# RP5_Left_Board.net
KiCad netlist of a schematic drawn in Altium Designer
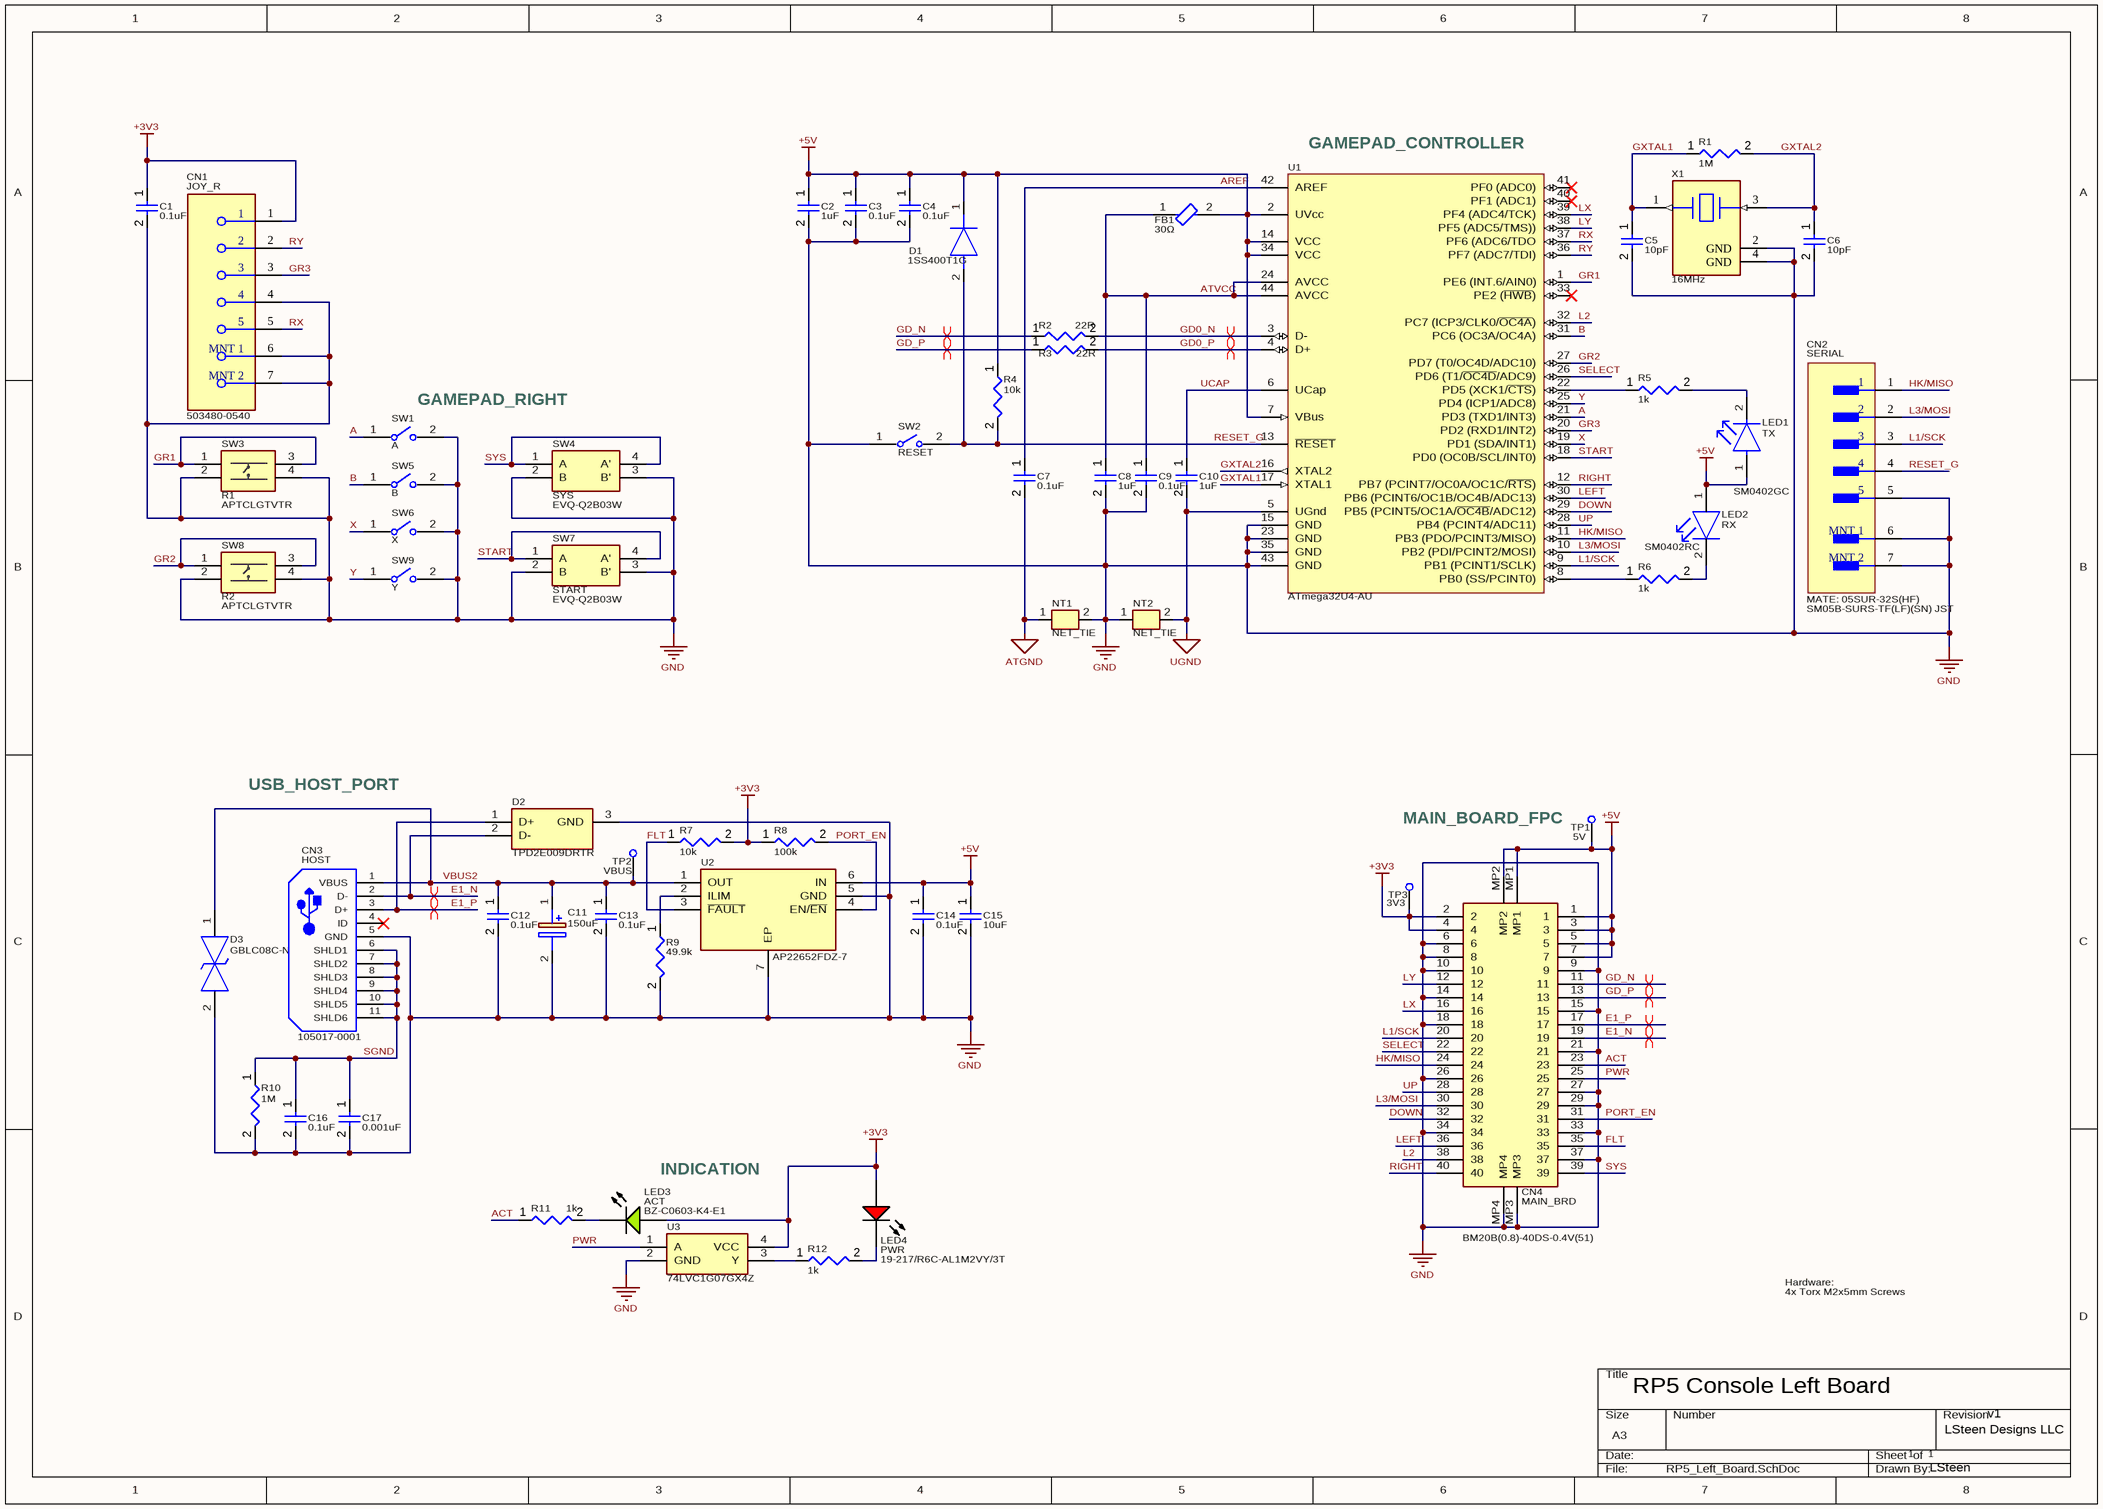
[diagram p0: RP5_Left_Board.SchDoc]

(export (version "E")
  (design (tool "Eeschema 10.0.6"))
  (components
    (comp (ref "C1")
      (value "0.1uF")
      (footprint "CAPC1005X56X25LL10T15")
      (description "Chip Capacitor, 0.1 uF, +/- 5%, 16 V, 0402 (1005 Metric)")
      (fields (field (name "TOLERANCE") "5%"))
      (libsource (lib "Colorado Technical University") (part "CAP-NP-2"))
    )
    (comp (ref "C2")
      (value "1uF")
      (footprint "CAPC0603(1608)100_L")
      (description "Chip Capacitor, 1uF +/-20%, 10V, 0603, Thickness 1 mm")
      (fields (field (name "TOLERANCE") "10%"))
      (libsource (lib "Colorado Technical University") (part "CAP-NP-2"))
    )
    (comp (ref "C3")
      (value "0.1uF")
      (footprint "CAPC1005X56X25LL10T15")
      (description "Chip Capacitor, 0.1 uF, +/- 5%, 16 V, 0402 (1005 Metric)")
      (fields (field (name "TOLERANCE") "5%"))
      (libsource (lib "Colorado Technical University") (part "CAP-NP-2"))
    )
    (comp (ref "C4")
      (value "0.1uF")
      (footprint "CAPC1005X56X25LL10T15")
      (description "Chip Capacitor, 0.1 uF, +/- 5%, 16 V, 0402 (1005 Metric)")
      (fields (field (name "TOLERANCE") "5%"))
      (libsource (lib "Colorado Technical University") (part "CAP-NP-2"))
    )
    (comp (ref "C5")
      (value "10pF")
      (footprint "CAPC1005X56X25LL10T15")
      (description "Chip Capacitor, 10 pF, +/- 5%, 16 V, 0402 (1005 Metric)")
      (fields (field (name "TOLERANCE") "5%"))
      (libsource (lib "Colorado Technical University") (part "CAP-NP-2"))
    )
    (comp (ref "C6")
      (value "10pF")
      (footprint "CAPC1005X56X25LL10T15")
      (description "Chip Capacitor, 10 pF, +/- 5%, 16 V, 0402 (1005 Metric)")
      (fields (field (name "TOLERANCE") "5%"))
      (libsource (lib "Colorado Technical University") (part "CAP-NP-2"))
    )
    (comp (ref "C7")
      (value "0.1uF")
      (footprint "CAPC1005X56X25LL10T15")
      (description "Chip Capacitor, 0.1 uF, +/- 5%, 16 V, 0402 (1005 Metric)")
      (fields (field (name "TOLERANCE") "5%"))
      (libsource (lib "Colorado Technical University") (part "CAP-NP-2"))
    )
    (comp (ref "C8")
      (value "1uF")
      (footprint "CAPC0603(1608)100_L")
      (description "Chip Capacitor, 1uF +/-20%, 10V, 0603, Thickness 1 mm")
      (fields (field (name "TOLERANCE") "10%"))
      (libsource (lib "Colorado Technical University") (part "CAP-NP-2"))
    )
    (comp (ref "C9")
      (value "0.1uF")
      (footprint "CAPC1005X56X25LL10T15")
      (description "Chip Capacitor, 0.1 uF, +/- 5%, 16 V, 0402 (1005 Metric)")
      (fields (field (name "TOLERANCE") "5%"))
      (libsource (lib "Colorado Technical University") (part "CAP-NP-2"))
    )
    (comp (ref "C10")
      (value "1uF")
      (footprint "CAPC0603(1608)100_L")
      (description "Chip Capacitor, 1uF +/-20%, 10V, 0603, Thickness 1 mm")
      (fields (field (name "TOLERANCE") "10%"))
      (libsource (lib "Colorado Technical University") (part "CAP-NP-2"))
    )
    (comp (ref "C11")
      (value "150uF")
      (footprint "SamacSys:CAPPM7344X310N")
      (description "Capacitor Polarised")
      (fields
        (field (name "MANUFACTURER_PART_NUMBER") "TPSD157K016S0125")
        (field (name "MOUSER PART NUMBER") "581-TPSD157K016S0125")
      )
      (libsource (lib "SamacSys") (part "TPSD157K016S0125"))
    )
    (comp (ref "C12")
      (value "0.1uF")
      (footprint "CAPC1005X56X25LL10T15")
      (description "Chip Capacitor, 0.1 uF, +/- 5%, 16 V, 0402 (1005 Metric)")
      (fields (field (name "TOLERANCE") "5%"))
      (libsource (lib "Colorado Technical University") (part "CAP-NP-2"))
    )
    (comp (ref "C13")
      (value "0.1uF")
      (footprint "CAPC1005X56X25LL10T15")
      (description "Chip Capacitor, 0.1 uF, +/- 5%, 16 V, 0402 (1005 Metric)")
      (fields (field (name "TOLERANCE") "5%"))
      (libsource (lib "Colorado Technical University") (part "CAP-NP-2"))
    )
    (comp (ref "C14")
      (value "0.1uF")
      (footprint "CAPC1005X56X25LL10T15")
      (description "Chip Capacitor, 0.1 uF, +/- 5%, 16 V, 0402 (1005 Metric)")
      (fields (field (name "TOLERANCE") "5%"))
      (libsource (lib "Colorado Technical University") (part "CAP-NP-2"))
    )
    (comp (ref "C15")
      (value "10uF")
      (footprint "CAPC0805(2012)145_L")
      (description "Chip Capacitor, 10µF +/-20%, 25V, 0805, Thickness 1.45 mm")
      (fields (field (name "TOLERANCE") "10%"))
      (libsource (lib "Colorado Technical University") (part "CAP-NP-2"))
    )
    (comp (ref "C16")
      (value "0.1uF")
      (footprint "CAPC1005X56X25LL10T15")
      (description "Chip Capacitor, 0.1 uF, +/- 5%, 16 V, 0402 (1005 Metric)")
      (fields (field (name "TOLERANCE") "5%"))
      (libsource (lib "Colorado Technical University") (part "CAP-NP-2"))
    )
    (comp (ref "C17")
      (value "0.001uF")
      (footprint "CAPC1005X56X25LL10T15")
      (description "Chip Capacitor, 0.1 uF, +/- 5%, 16 V, 0402 (1005 Metric)")
      (fields (field (name "TOLERANCE") "5%"))
      (libsource (lib "Colorado Technical University") (part "CAP-NP-2"))
    )
    (comp (ref "CN1")
      (value "JOY_R")
      (footprint "FP-503480-0540-MFG")
      (description "503480-0540 Connector FFC/FPC SKT 5 Position 0.5mm Solder Right Angle Surface Mount T/R")
      (libsource (lib "Altium Content Vault") (part "6b037d2877ced340e1c65ac82253790"))
    )
    (comp (ref "CN2")
      (value "SERIAL")
      (footprint "FP-SM05B-SURS-TF_LF_SN-MFG")
      (description "CONN HEADER SMD R/A 5POS 0.8MM")
      (libsource (lib "Altium Content Vault") (part "SM05B-SURS-TF_LF_SN"))
    )
    (comp (ref "CN3")
      (value "HOST")
      (footprint "105017-0001")
      (description "Micro USB Connector")
      (fields
        (field (name "MANUFACTURER_PART_NUMBER") "105017-0001")
        (field (name "MOUSER PART NUMBER") "538-105017-0001")
      )
      (libsource (lib "SamacSys") (part "105017-0001"))
    )
    (comp (ref "CN4")
      (value "MAIN_BRD")
      (footprint "SamacSys:BM20B0840DS04V51")
      (description "Connector")
      (fields
        (field (name "MANUFACTURER_PART_NUMBER") "BM20B(0.8)-40DS-0.4V(51)")
        (field (name "MOUSER PART NUMBER") "798-BM20B0840DS04V51")
      )
      (libsource (lib "SamacSys") (part "BM20B(0.8)-40DS-0.4V(51)"))
    )
    (comp (ref "D1")
      (value "1SS400T1G")
      (footprint "SamacSys:SODFL1608X70N")
      (description "Diode")
      (fields (field (name "MOUSER PART NUMBER") "863-1SS400T1G"))
      (libsource (lib "SamacSys") (part "1SS400T1G"))
    )
    (comp (ref "D2")
      (value "TPD2E009DRTR")
      (footprint "SamacSys:SOTFL35P100X50-3N")
      (description "Integrated Circuit")
      (fields (field (name "MOUSER PART NUMBER") "595-TPD2E009DRTR"))
      (libsource (lib "SamacSys") (part "TPD2E009DRTR"))
    )
    (comp (ref "D3")
      (value "GBLC08C-N")
      (footprint "SOD-323_L1.8-W1.3-LS2.5-BI")
      (description "ESD DIODE-BI_LCSC#C314256")
      (libsource (lib "Schlib1") (part "GBLC08C-N"))
    )
    (comp (ref "FB1")
      (value "30Ω")
      (footprint "FP-MH2029-MFG")
      (description "FERRITE BEAD 30 OHM 0805 1LN")
      (fields
        (field (name "MANUFACTURER PART NUMBER") "MH2029-300Y")
        (field (name "OCTOPART") "https://octopart.com/mh2029-300y-bourns-756929")
      )
      (libsource (lib "Altium Content Vault") (part "5f30dd21d616792df468990f7003faa"))
    )
    (comp (ref "LED1")
      (value "TX")
      (footprint "FP-SM0402GC-MFG")
      (description "LED GREEN CLEAR 0402 SMD SUPPLIMENT LCSC MHT136CGCT")
      (libsource (lib "") (part "ab1c01a81903e929fc6c44469aada92_1"))
    )
    (comp (ref "LED2")
      (value "RX")
      (footprint "FP-SM0402RC-MFG")
      (description "LED RED CLEAR 0402 SMD SUPPLIMENT LCSC MHT136CRCT")
      (libsource (lib "Altium Content Vault") (part "ab1c01a81903e929fc6c44469aada92"))
    )
    (comp (ref "LED3")
      (value "ACT")
      (footprint "LED_0603")
      (fields (field (name "MPN") "BZ-C0603-K4-E1"))
      (libsource (lib "SamacSys") (part "BZ-C0603-K4-E1"))
    )
    (comp (ref "LED4")
      (value "PWR")
      (footprint "EVRL-0603-2_V")
      (description "Chip LED, Red, 5 V, 25 mA, -40 to 85 degC, 2-Pin SMD (0603), RoHS, Tape and Reel")
      (fields
        (field (name "MANUFACTURER") "Everlight Electronics")
        (field (name "MANUFACTURER PART NUMBER") "19-217/R6C-AL1M2VY/3T")
      )
      (libsource (lib "Altium Content Vault") (part "LED-RED-AK-2"))
    )
    (comp (ref "NT1") (value "NET_TIE") (footprint "NET_TIE1") (libsource (lib "Schlib1") (part "NET_TIE")))
    (comp (ref "NT2") (value "NET_TIE") (footprint "NET_TIE1") (libsource (lib "Schlib1") (part "NET_TIE")))
    (comp (ref "R1")
      (value "1M")
      (footprint "RESC0402(1005)_L")
      (description "Chip Resistor, 1 MOhms, +/-5 %, 63 mW, -55 to 155 degC, 0402")
      (fields (field (name "TOLERANCE") "5%") (field (name "POWER") "63mW"))
      (libsource (lib "Colorado Technical University") (part "RES-2"))
    )
    (comp (ref "R2")
      (value "22R")
      (footprint "RESC0402(1005)_L")
      (description "Chip Resistor, 22 Ohms, +/-5 %, 63 mW, -55 to 155 degC, 0402")
      (fields (field (name "TOLERANCE") "5%") (field (name "POWER") "63mW"))
      (libsource (lib "Colorado Technical University") (part "RES-2"))
    )
    (comp (ref "R3")
      (value "22R")
      (footprint "RESC0402(1005)_L")
      (description "Chip Resistor, 22 Ohms, +/-5 %, 63 mW, -55 to 155 degC, 0402")
      (fields (field (name "TOLERANCE") "5%") (field (name "POWER") "63mW"))
      (libsource (lib "Colorado Technical University") (part "RES-2"))
    )
    (comp (ref "R4")
      (value "10k")
      (footprint "RESC0402(1005)_L")
      (description "Chip Resistor, 10 kOhms, +/-5 %, 63 mW, -55 to 155 degC, 0402")
      (fields (field (name "TOLERANCE") "5%") (field (name "POWER") "63mW"))
      (libsource (lib "Colorado Technical University") (part "RES-2"))
    )
    (comp (ref "R5")
      (value "1k")
      (footprint "RESC0402(1005)_L")
      (description "Chip Resistor, 1 kOhms, +/-5 %, 63 mW, -55 to 155 degC, 0402")
      (fields (field (name "TOLERANCE") "5%") (field (name "POWER") "63mW"))
      (libsource (lib "Colorado Technical University") (part "RES-2"))
    )
    (comp (ref "R6")
      (value "1k")
      (footprint "RESC0402(1005)_L")
      (description "Chip Resistor, 1 kOhms, +/-5 %, 63 mW, -55 to 155 degC, 0402")
      (fields (field (name "TOLERANCE") "5%") (field (name "POWER") "63mW"))
      (libsource (lib "Colorado Technical University") (part "RES-2"))
    )
    (comp (ref "R7")
      (value "10k")
      (footprint "RESC0402(1005)_L")
      (description "Chip Resistor, 10 kOhms, +/-5 %, 63 mW, -55 to 155 degC, 0402")
      (fields (field (name "TOLERANCE") "5%") (field (name "POWER") "63mW"))
      (libsource (lib "Colorado Technical University") (part "RES-2"))
    )
    (comp (ref "R8")
      (value "100k")
      (footprint "RESC0402(1005)_L")
      (description "Chip Resistor, 100 kOhms, +/-5 %, 63 mW, -55 to 155 degC, 0402")
      (fields (field (name "TOLERANCE") "5%") (field (name "POWER") "63mW"))
      (libsource (lib "Colorado Technical University") (part "RES-2"))
    )
    (comp (ref "R9")
      (value "49.9k")
      (footprint "RESC0402(1005)_L")
      (description "Chip Resistor, 49.9 kOhms, +/-5 %, 63 mW, -55 to 155 degC, 0402")
      (fields (field (name "TOLERANCE") "5%") (field (name "POWER") "63mW"))
      (libsource (lib "Colorado Technical University") (part "RES-2"))
    )
    (comp (ref "R10")
      (value "1M")
      (footprint "RESC0402(1005)_L")
      (description "Chip Resistor, 1 MOhms, +/-5 %, 63 mW, -55 to 155 degC, 0402")
      (fields (field (name "TOLERANCE") "5%") (field (name "POWER") "63mW"))
      (libsource (lib "Colorado Technical University") (part "RES-2"))
    )
    (comp (ref "R11")
      (value "1k")
      (footprint "RESC0402(1005)_L")
      (description "Chip Resistor, 1 kOhms, +/-5 %, 63 mW, -55 to 155 degC, 0402")
      (fields (field (name "TOLERANCE") "5%") (field (name "POWER") "63mW"))
      (libsource (lib "Colorado Technical University") (part "RES-2"))
    )
    (comp (ref "R12")
      (value "1k")
      (footprint "RESC0402(1005)_L")
      (description "Chip Resistor, 1 kOhms, +/-5 %, 63 mW, -55 to 155 degC, 0402")
      (fields (field (name "TOLERANCE") "5%") (field (name "POWER") "63mW"))
      (libsource (lib "Colorado Technical University") (part "RES-2"))
    )
    (comp (ref "SW1")
      (value "A")
      (footprint "L4.0-W4.0-CNDV-PAD")
      (description "Conductive Pad Switch")
      (libsource (lib "Schlib1") (part "CNDV_SW"))
    )
    (comp (ref "SW2")
      (value "RESET")
      (footprint "FP-B3U-1000P-MFG")
      (description "LCSC SWITCH TACTILE SPST-NO 0.05A 12V")
      (libsource (lib "Altium Content Vault") (part "ae622034201233ca1abcedc05908f33"))
    )
    (comp (ref "SW3")
      (value "R1")
      (footprint "SamacSys:APTCLGTVTR")
      (description "Switch")
      (fields
        (field (name "MANUFACTURER_PART_NUMBER") "APTCLGTVTR")
        (field (name "MOUSER PART NUMBER") "642-APTCLGTVTR")
      )
      (libsource (lib "SamacSys") (part "APTCLGTVTR"))
    )
    (comp (ref "SW4")
      (value "SYS")
      (footprint "SamacSys:EVQQ2")
      (description "Switch")
      (fields
        (field (name "MANUFACTURER_PART_NUMBER") "EVQ-Q2B03W")
        (field (name "MOUSER PART NUMBER") "667-EVQ-Q2B03W")
      )
      (libsource (lib "SamacSys") (part "EVQ-Q2B03W"))
    )
    (comp (ref "SW5")
      (value "B")
      (footprint "L4.0-W4.0-CNDV-PAD")
      (description "Conductive Pad Switch")
      (libsource (lib "Schlib1") (part "CNDV_SW"))
    )
    (comp (ref "SW6")
      (value "X")
      (footprint "L4.0-W4.0-CNDV-PAD")
      (description "Conductive Pad Switch")
      (libsource (lib "Schlib1") (part "CNDV_SW"))
    )
    (comp (ref "SW7")
      (value "START")
      (footprint "SamacSys:EVQQ2")
      (description "Switch")
      (fields
        (field (name "MANUFACTURER_PART_NUMBER") "EVQ-Q2B03W")
        (field (name "MOUSER PART NUMBER") "667-EVQ-Q2B03W")
      )
      (libsource (lib "SamacSys") (part "EVQ-Q2B03W"))
    )
    (comp (ref "SW8")
      (value "R2")
      (footprint "APTCLGTVTR_No_Holes")
      (description "Switch")
      (fields
        (field (name "MANUFACTURER_PART_NUMBER") "APTCLGTVTR")
        (field (name "MOUSER PART NUMBER") "642-APTCLGTVTR")
      )
      (libsource (lib "SamacSys") (part "APTCLGTVTR_NH"))
    )
    (comp (ref "SW9")
      (value "Y")
      (footprint "L4.0-W4.0-CNDV-PAD")
      (description "Conductive Pad Switch")
      (libsource (lib "Schlib1") (part "CNDV_SW"))
    )
    (comp (ref "TP1")
      (value "5V")
      (footprint "TP")
      (description "TestPoint")
      (libsource (lib "Schlib1") (part "TestPoint"))
    )
    (comp (ref "TP2")
      (value "VBUS")
      (footprint "TP")
      (description "TestPoint")
      (libsource (lib "Schlib1") (part "TestPoint"))
    )
    (comp (ref "TP3")
      (value "3V3")
      (footprint "TP")
      (description "TestPoint")
      (libsource (lib "Schlib1") (part "TestPoint"))
    )
    (comp (ref "U1")
      (value "ATmega32U4-AU")
      (footprint "44ML_M")
      (libsource (lib "Altium Content Vault") (part "MC-8B-ATM16U4-SQ44"))
    )
    (comp (ref "U2")
      (value "AP22652FDZ-7")
      (footprint "SamacSys:SON65P200X200X80-7N-D")
      (description "Integrated Circuit")
      (fields (field (name "MOUSER PART NUMBER") "621-AP22652FDZ-7"))
      (libsource (lib "SamacSys") (part "AP22652FDZ-7"))
    )
    (comp (ref "U3")
      (value "74LVC1G07GX4Z")
      (footprint "SamacSys:74LVC1G07GX4Z")
      (description "Integrated Circuit")
      (fields (field (name "MOUSER PART NUMBER") "771-74LVC1G07GX4Z"))
      (libsource (lib "SamacSys") (part "74LVC1G07GX4Z"))
    )
    (comp (ref "X1")
      (value "16MHz")
      (footprint "FP-ABM8G-MFG")
      (description "Crystal 16MHz ±30ppm (Tol) ±30ppm (Stability) 10pF FUND 80Ω 4-Pin SMD T/R")
      (fields (field (name "TOLERANCE") "30ppm"))
      (libsource (lib "Altium Content Vault") (part "48e526d86b7f2615d98721063c72f49"))
    )
  )
  (nets
    (net (code "1") (name "+3V3") (class "Default")
      (node (ref "C1") (pin "1") (pinfunction "1_1") (pintype "passive"))
      (node (ref "CN1") (pin "1") (pinfunction "1_1") (pintype "passive"))
      (node (ref "CN4") (pin "2") (pinfunction "2_2") (pintype "passive"))
      (node (ref "CN4") (pin "4") (pinfunction "4_4") (pintype "passive"))
      (node (ref "LED3") (pin "1") (pinfunction "A_1") (pintype "passive"))
      (node (ref "LED4") (pin "1") (pinfunction "A_1") (pintype "passive"))
      (node (ref "R7") (pin "2") (pinfunction "2_2") (pintype "passive"))
      (node (ref "R8") (pin "1") (pinfunction "1_1") (pintype "passive"))
      (node (ref "TP3") (pin "1") (pinfunction "1_1") (pintype "passive"))
      (node (ref "U3") (pin "4") (pinfunction "VCC_4") (pintype "passive"))
    )
    (net (code "2") (name "+5V") (class "Default")
      (node (ref "C14") (pin "1") (pinfunction "1_1") (pintype "passive"))
      (node (ref "C15") (pin "1") (pinfunction "1_1") (pintype "passive"))
      (node (ref "C2") (pin "1") (pinfunction "1_1") (pintype "passive"))
      (node (ref "C3") (pin "1") (pinfunction "1_1") (pintype "passive"))
      (node (ref "C4") (pin "1") (pinfunction "1_1") (pintype "passive"))
      (node (ref "CN4") (pin "1") (pinfunction "1_1") (pintype "passive"))
      (node (ref "CN4") (pin "3") (pinfunction "3_3") (pintype "passive"))
      (node (ref "CN4") (pin "5") (pinfunction "5_5") (pintype "passive"))
      (node (ref "CN4") (pin "7") (pinfunction "7_7") (pintype "passive"))
      (node (ref "CN4") (pin "MP1") (pinfunction "MP1_MP1") (pintype "passive"))
      (node (ref "CN4") (pin "MP2") (pinfunction "MP2_MP2") (pintype "passive"))
      (node (ref "D1") (pin "1") (pinfunction "K_1") (pintype "passive"))
      (node (ref "FB1") (pin "2") (pinfunction "2_2") (pintype "passive"))
      (node (ref "LED1") (pin "1") (pinfunction "A_1") (pintype "passive"))
      (node (ref "LED2") (pin "1") (pinfunction "A_1") (pintype "passive"))
      (node (ref "R4") (pin "1") (pinfunction "1_1") (pintype "passive"))
      (node (ref "TP1") (pin "1") (pinfunction "1_1") (pintype "passive"))
      (node (ref "U1") (pin "14") (pinfunction "VCC_14") (pintype "power_in"))
      (node (ref "U1") (pin "2") (pinfunction "UVcc_2") (pintype "power_in"))
      (node (ref "U1") (pin "34") (pinfunction "VCC_34") (pintype "power_in"))
      (node (ref "U1") (pin "7") (pinfunction "VBus_7") (pintype "input"))
      (node (ref "U2") (pin "6") (pinfunction "IN_6") (pintype "passive"))
    )
    (net (code "4") (name "/A") (class "Default")
      (node (ref "SW1") (pin "1") (pinfunction "1_1") (pintype "passive"))
      (node (ref "U1") (pin "21") (pinfunction "PD3_(TXD1/INT3)_21") (pintype "bidirectional"))
    )
    (net (code "5") (name "/ACT") (class "Default")
      (node (ref "CN4") (pin "23") (pinfunction "23_23") (pintype "passive"))
      (node (ref "R11") (pin "1") (pinfunction "1_1") (pintype "passive"))
    )
    (net (code "6") (name "/AREF") (class "Default")
      (node (ref "C7") (pin "1") (pinfunction "1_1") (pintype "passive"))
      (node (ref "U1") (pin "42") (pinfunction "AREF_42") (pintype "passive"))
    )
    (net (code "7") (name "/ATVCC") (class "Default")
      (node (ref "C8") (pin "1") (pinfunction "1_1") (pintype "passive"))
      (node (ref "C9") (pin "1") (pinfunction "1_1") (pintype "passive"))
      (node (ref "FB1") (pin "1") (pinfunction "1_1") (pintype "passive"))
      (node (ref "U1") (pin "24") (pinfunction "AVCC_24") (pintype "power_in"))
      (node (ref "U1") (pin "44") (pinfunction "AVCC_44") (pintype "power_in"))
    )
    (net (code "8") (name "/B") (class "Default")
      (node (ref "SW5") (pin "1") (pinfunction "1_1") (pintype "passive"))
      (node (ref "U1") (pin "31") (pinfunction "PC6_(OC3A/OC4A)_31") (pintype "bidirectional"))
    )
    (net (code "9") (name "/DOWN") (class "Default")
      (node (ref "CN4") (pin "32") (pinfunction "32_32") (pintype "passive"))
      (node (ref "U1") (pin "29") (pinfunction "PB5_(PCINT5/OC1A/~{OC4B}/ADC12)_29") (pintype "bidirectional"))
    )
    (net (code "10") (name "/E1_N") (class "Default")
      (node (ref "CN3") (pin "2") (pinfunction "D-_2") (pintype "passive"))
      (node (ref "CN4") (pin "19") (pinfunction "19_19") (pintype "passive"))
      (node (ref "D2") (pin "2") (pinfunction "D-_2") (pintype "passive"))
    )
    (net (code "11") (name "/E1_P") (class "Default")
      (node (ref "CN3") (pin "3") (pinfunction "D+_3") (pintype "passive"))
      (node (ref "CN4") (pin "17") (pinfunction "17_17") (pintype "passive"))
      (node (ref "D2") (pin "1") (pinfunction "D+_1") (pintype "passive"))
    )
    (net (code "12") (name "/FLT") (class "Default")
      (node (ref "CN4") (pin "35") (pinfunction "35_35") (pintype "passive"))
      (node (ref "R7") (pin "1") (pinfunction "1_1") (pintype "passive"))
      (node (ref "U2") (pin "3") (pinfunction "~{FAULT}_3") (pintype "passive"))
    )
    (net (code "13") (name "/GD0_N") (class "Default")
      (node (ref "R2") (pin "2") (pinfunction "2_2") (pintype "passive"))
      (node (ref "U1") (pin "3") (pinfunction "D-_3") (pintype "bidirectional"))
    )
    (net (code "14") (name "/GD0_P") (class "Default")
      (node (ref "R3") (pin "2") (pinfunction "2_2") (pintype "passive"))
      (node (ref "U1") (pin "4") (pinfunction "D+_4") (pintype "bidirectional"))
    )
    (net (code "15") (name "/GD_N") (class "Default")
      (node (ref "CN4") (pin "11") (pinfunction "11_11") (pintype "passive"))
      (node (ref "R2") (pin "1") (pinfunction "1_1") (pintype "passive"))
    )
    (net (code "16") (name "/GD_P") (class "Default")
      (node (ref "CN4") (pin "13") (pinfunction "13_13") (pintype "passive"))
      (node (ref "R3") (pin "1") (pinfunction "1_1") (pintype "passive"))
    )
    (net (code "17") (name "/GR1") (class "Default")
      (node (ref "SW3") (pin "1") (pinfunction "1_1") (pintype "passive"))
      (node (ref "SW3") (pin "3") (pinfunction "3_3") (pintype "passive"))
      (node (ref "U1") (pin "1") (pinfunction "PE6_(INT.6/AIN0)_1") (pintype "bidirectional"))
    )
    (net (code "18") (name "/GR2") (class "Default")
      (node (ref "SW8") (pin "1") (pinfunction "1_1") (pintype "passive"))
      (node (ref "SW8") (pin "3") (pinfunction "3_3") (pintype "passive"))
      (node (ref "U1") (pin "27") (pinfunction "PD7_(T0/OC4D/ADC10)_27") (pintype "bidirectional"))
    )
    (net (code "19") (name "/GR3") (class "Default")
      (node (ref "CN1") (pin "3") (pinfunction "3_3") (pintype "passive"))
      (node (ref "U1") (pin "20") (pinfunction "PD2_(RXD1/INT2)_20") (pintype "bidirectional"))
    )
    (net (code "20") (name "/GXTAL1") (class "Default")
      (node (ref "C5") (pin "1") (pinfunction "1_1") (pintype "passive"))
      (node (ref "R1") (pin "1") (pinfunction "1_1") (pintype "passive"))
      (node (ref "U1") (pin "17") (pinfunction "XTAL1_17") (pintype "input"))
      (node (ref "X1") (pin "1") (pinfunction "1_1") (pintype "output"))
    )
    (net (code "21") (name "/GXTAL2") (class "Default")
      (node (ref "C6") (pin "1") (pinfunction "1_1") (pintype "passive"))
      (node (ref "R1") (pin "2") (pinfunction "2_2") (pintype "passive"))
      (node (ref "U1") (pin "16") (pinfunction "XTAL2_16") (pintype "output"))
      (node (ref "X1") (pin "3") (pinfunction "3_3") (pintype "input"))
    )
    (net (code "22") (name "/HK{slash}MISO") (class "Default")
      (node (ref "CN2") (pin "1") (pinfunction "1_1") (pintype "passive"))
      (node (ref "CN4") (pin "24") (pinfunction "24_24") (pintype "passive"))
      (node (ref "U1") (pin "11") (pinfunction "PB3_(PDO/PCINT3/MISO)_11") (pintype "bidirectional"))
    )
    (net (code "23") (name "/L1{slash}SCK") (class "Default")
      (node (ref "CN2") (pin "3") (pinfunction "3_3") (pintype "passive"))
      (node (ref "CN4") (pin "20") (pinfunction "20_20") (pintype "passive"))
      (node (ref "U1") (pin "9") (pinfunction "PB1_(PCINT1/SCLK)_9") (pintype "bidirectional"))
    )
    (net (code "24") (name "/L2") (class "Default")
      (node (ref "CN4") (pin "38") (pinfunction "38_38") (pintype "passive"))
      (node (ref "U1") (pin "32") (pinfunction "PC7_(ICP3/CLK0/~{OC4A})_32") (pintype "bidirectional"))
    )
    (net (code "25") (name "/L3{slash}MOSI") (class "Default")
      (node (ref "CN2") (pin "2") (pinfunction "2_2") (pintype "passive"))
      (node (ref "CN4") (pin "30") (pinfunction "30_30") (pintype "passive"))
      (node (ref "U1") (pin "10") (pinfunction "PB2_(PDI/PCINT2/MOSI)_10") (pintype "bidirectional"))
    )
    (net (code "26") (name "/LEFT") (class "Default")
      (node (ref "CN4") (pin "36") (pinfunction "36_36") (pintype "passive"))
      (node (ref "U1") (pin "30") (pinfunction "PB6_(PCINT6/OC1B/OC4B/ADC13)_30") (pintype "bidirectional"))
    )
    (net (code "27") (name "/LX") (class "Default")
      (node (ref "CN4") (pin "16") (pinfunction "16_16") (pintype "passive"))
      (node (ref "U1") (pin "39") (pinfunction "PF4_(ADC4/TCK)_39") (pintype "bidirectional"))
    )
    (net (code "28") (name "/LY") (class "Default")
      (node (ref "CN4") (pin "12") (pinfunction "12_12") (pintype "passive"))
      (node (ref "U1") (pin "38") (pinfunction "PF5_(ADC5/TMS))_38") (pintype "bidirectional"))
    )
    (net (code "29") (name "/PORT_EN") (class "Default")
      (node (ref "CN4") (pin "31") (pinfunction "31_31") (pintype "passive"))
      (node (ref "R8") (pin "2") (pinfunction "2_2") (pintype "passive"))
      (node (ref "U2") (pin "4") (pinfunction "EN/~{EN}_4") (pintype "passive"))
    )
    (net (code "30") (name "/PWR") (class "Default")
      (node (ref "CN4") (pin "25") (pinfunction "25_25") (pintype "passive"))
      (node (ref "U3") (pin "1") (pinfunction "A_1") (pintype "passive"))
    )
    (net (code "31") (name "/RESET_G") (class "Default")
      (node (ref "CN2") (pin "4") (pinfunction "4_4") (pintype "passive"))
      (node (ref "D1") (pin "2") (pinfunction "A_2") (pintype "passive"))
      (node (ref "R4") (pin "2") (pinfunction "2_2") (pintype "passive"))
      (node (ref "SW2") (pin "2") (pinfunction "2_2") (pintype "passive"))
      (node (ref "U1") (pin "13") (pinfunction "~{RESET}_13") (pintype "passive"))
    )
    (net (code "32") (name "/RIGHT") (class "Default")
      (node (ref "CN4") (pin "40") (pinfunction "40_40") (pintype "passive"))
      (node (ref "U1") (pin "12") (pinfunction "PB7_(PCINT7/OC0A/OC1C/~{RTS})_12") (pintype "bidirectional"))
    )
    (net (code "33") (name "/RX") (class "Default")
      (node (ref "CN1") (pin "5") (pinfunction "5_5") (pintype "passive"))
      (node (ref "U1") (pin "37") (pinfunction "PF6_(ADC6/TDO_37") (pintype "bidirectional"))
    )
    (net (code "34") (name "/RY") (class "Default")
      (node (ref "CN1") (pin "2") (pinfunction "2_2") (pintype "passive"))
      (node (ref "U1") (pin "36") (pinfunction "PF7_(ADC7/TDI)_36") (pintype "bidirectional"))
    )
    (net (code "35") (name "/SELECT") (class "Default")
      (node (ref "CN4") (pin "22") (pinfunction "22_22") (pintype "passive"))
      (node (ref "U1") (pin "26") (pinfunction "PD6_(T1/~{OC4D}/ADC9)_26") (pintype "bidirectional"))
    )
    (net (code "36") (name "/SGND") (class "Default")
      (node (ref "C16") (pin "1") (pinfunction "1_1") (pintype "passive"))
      (node (ref "C17") (pin "1") (pinfunction "1_1") (pintype "passive"))
      (node (ref "CN3") (pin "10") (pinfunction "SHLD5_10") (pintype "passive"))
      (node (ref "CN3") (pin "11") (pinfunction "SHLD6_11") (pintype "passive"))
      (node (ref "CN3") (pin "6") (pinfunction "SHLD1_6") (pintype "passive"))
      (node (ref "CN3") (pin "7") (pinfunction "SHLD2_7") (pintype "passive"))
      (node (ref "CN3") (pin "8") (pinfunction "SHLD3_8") (pintype "passive"))
      (node (ref "CN3") (pin "9") (pinfunction "SHLD4_9") (pintype "passive"))
      (node (ref "R10") (pin "1") (pinfunction "1_1") (pintype "passive"))
    )
    (net (code "37") (name "/START") (class "Default")
      (node (ref "SW7") (pin "1") (pinfunction "A_1") (pintype "passive"))
      (node (ref "SW7") (pin "4") (pinfunction "A'_4") (pintype "passive"))
      (node (ref "U1") (pin "18") (pinfunction "PD0_(OC0B/SCL/INT0)_18") (pintype "bidirectional"))
    )
    (net (code "38") (name "/SYS") (class "Default")
      (node (ref "CN4") (pin "39") (pinfunction "39_39") (pintype "passive"))
      (node (ref "SW4") (pin "1") (pinfunction "A_1") (pintype "passive"))
      (node (ref "SW4") (pin "4") (pinfunction "A'_4") (pintype "passive"))
    )
    (net (code "39") (name "/UCAP") (class "Default")
      (node (ref "C10") (pin "1") (pinfunction "1_1") (pintype "passive"))
      (node (ref "U1") (pin "6") (pinfunction "UCap_6") (pintype "passive"))
    )
    (net (code "40") (name "/UP") (class "Default")
      (node (ref "CN4") (pin "28") (pinfunction "28_28") (pintype "passive"))
      (node (ref "U1") (pin "28") (pinfunction "PB4_(PCINT4/ADC11)_28") (pintype "bidirectional"))
    )
    (net (code "41") (name "/VBUS2") (class "Default")
      (node (ref "C11") (pin "1") (pinfunction "+_1") (pintype "passive"))
      (node (ref "C12") (pin "1") (pinfunction "1_1") (pintype "passive"))
      (node (ref "C13") (pin "1") (pinfunction "1_1") (pintype "passive"))
      (node (ref "CN3") (pin "1") (pinfunction "VBUS_1") (pintype "passive"))
      (node (ref "D3") (pin "1") (pinfunction "1_1") (pintype "passive"))
      (node (ref "TP2") (pin "1") (pinfunction "1_1") (pintype "passive"))
      (node (ref "U2") (pin "1") (pinfunction "OUT_1") (pintype "passive"))
    )
    (net (code "42") (name "/X") (class "Default")
      (node (ref "SW6") (pin "1") (pinfunction "1_1") (pintype "passive"))
      (node (ref "U1") (pin "19") (pinfunction "PD1_(SDA/INT1)_19") (pintype "bidirectional"))
    )
    (net (code "43") (name "/Y") (class "Default")
      (node (ref "SW9") (pin "1") (pinfunction "1_1") (pintype "passive"))
      (node (ref "U1") (pin "25") (pinfunction "PD4_(ICP1/ADC8)_25") (pintype "bidirectional"))
    )
    (net (code "44") (name "ATGND") (class "Default")
      (node (ref "C7") (pin "2") (pinfunction "2_2") (pintype "passive"))
      (node (ref "NT1") (pin "1") (pintype "passive"))
    )
    (net (code "45") (name "GND") (class "Default")
      (node (ref "C1") (pin "2") (pinfunction "2_2") (pintype "passive"))
      (node (ref "C11") (pin "2") (pinfunction "-_2") (pintype "passive"))
      (node (ref "C12") (pin "2") (pinfunction "2_2") (pintype "passive"))
      (node (ref "C13") (pin "2") (pinfunction "2_2") (pintype "passive"))
      (node (ref "C14") (pin "2") (pinfunction "2_2") (pintype "passive"))
      (node (ref "C15") (pin "2") (pinfunction "2_2") (pintype "passive"))
      (node (ref "C16") (pin "2") (pinfunction "2_2") (pintype "passive"))
      (node (ref "C17") (pin "2") (pinfunction "2_2") (pintype "passive"))
      (node (ref "C2") (pin "2") (pinfunction "2_2") (pintype "passive"))
      (node (ref "C3") (pin "2") (pinfunction "2_2") (pintype "passive"))
      (node (ref "C4") (pin "2") (pinfunction "2_2") (pintype "passive"))
      (node (ref "C5") (pin "2") (pinfunction "2_2") (pintype "passive"))
      (node (ref "C6") (pin "2") (pinfunction "2_2") (pintype "passive"))
      (node (ref "C8") (pin "2") (pinfunction "2_2") (pintype "passive"))
      (node (ref "C9") (pin "2") (pinfunction "2_2") (pintype "passive"))
      (node (ref "CN1") (pin "4") (pinfunction "4_4") (pintype "passive"))
      (node (ref "CN1") (pin "6") (pinfunction "MNT_1_6") (pintype "passive"))
      (node (ref "CN1") (pin "7") (pinfunction "MNT_2_7") (pintype "passive"))
      (node (ref "CN2") (pin "5") (pinfunction "5_5") (pintype "passive"))
      (node (ref "CN2") (pin "6") (pinfunction "MNT_1_6") (pintype "passive"))
      (node (ref "CN2") (pin "7") (pinfunction "MNT_2_7") (pintype "passive"))
      (node (ref "CN3") (pin "5") (pinfunction "GND_5") (pintype "passive"))
      (node (ref "CN4") (pin "10") (pinfunction "10_10") (pintype "passive"))
      (node (ref "CN4") (pin "14") (pinfunction "14_14") (pintype "passive"))
      (node (ref "CN4") (pin "15") (pinfunction "15_15") (pintype "passive"))
      (node (ref "CN4") (pin "18") (pinfunction "18_18") (pintype "passive"))
      (node (ref "CN4") (pin "21") (pinfunction "21_21") (pintype "passive"))
      (node (ref "CN4") (pin "26") (pinfunction "26_26") (pintype "passive"))
      (node (ref "CN4") (pin "27") (pinfunction "27_27") (pintype "passive"))
      (node (ref "CN4") (pin "29") (pinfunction "29_29") (pintype "passive"))
      (node (ref "CN4") (pin "33") (pinfunction "33_33") (pintype "passive"))
      (node (ref "CN4") (pin "34") (pinfunction "34_34") (pintype "passive"))
      (node (ref "CN4") (pin "37") (pinfunction "37_37") (pintype "passive"))
      (node (ref "CN4") (pin "6") (pinfunction "6_6") (pintype "passive"))
      (node (ref "CN4") (pin "8") (pinfunction "8_8") (pintype "passive"))
      (node (ref "CN4") (pin "9") (pinfunction "9_9") (pintype "passive"))
      (node (ref "CN4") (pin "MP3") (pinfunction "MP3_MP3") (pintype "passive"))
      (node (ref "CN4") (pin "MP4") (pinfunction "MP4_MP4") (pintype "passive"))
      (node (ref "D2") (pin "3") (pinfunction "GND_3") (pintype "passive"))
      (node (ref "D3") (pin "2") (pinfunction "2_2") (pintype "passive"))
      (node (ref "NT1") (pin "2") (pintype "passive"))
      (node (ref "NT2") (pin "1") (pintype "passive"))
      (node (ref "R10") (pin "2") (pinfunction "2_2") (pintype "passive"))
      (node (ref "R9") (pin "2") (pinfunction "2_2") (pintype "passive"))
      (node (ref "SW1") (pin "2") (pinfunction "2_2") (pintype "passive"))
      (node (ref "SW2") (pin "1") (pinfunction "1_1") (pintype "passive"))
      (node (ref "SW3") (pin "2") (pinfunction "2_2") (pintype "passive"))
      (node (ref "SW3") (pin "4") (pinfunction "4_4") (pintype "passive"))
      (node (ref "SW4") (pin "2") (pinfunction "B_2") (pintype "passive"))
      (node (ref "SW4") (pin "3") (pinfunction "B'_3") (pintype "passive"))
      (node (ref "SW5") (pin "2") (pinfunction "2_2") (pintype "passive"))
      (node (ref "SW6") (pin "2") (pinfunction "2_2") (pintype "passive"))
      (node (ref "SW7") (pin "2") (pinfunction "B_2") (pintype "passive"))
      (node (ref "SW7") (pin "3") (pinfunction "B'_3") (pintype "passive"))
      (node (ref "SW8") (pin "2") (pinfunction "2_2") (pintype "passive"))
      (node (ref "SW8") (pin "4") (pinfunction "4_4") (pintype "passive"))
      (node (ref "SW9") (pin "2") (pinfunction "2_2") (pintype "passive"))
      (node (ref "U1") (pin "15") (pinfunction "GND_15") (pintype "power_in"))
      (node (ref "U1") (pin "23") (pinfunction "GND_23") (pintype "power_in"))
      (node (ref "U1") (pin "35") (pinfunction "GND_35") (pintype "power_in"))
      (node (ref "U1") (pin "43") (pinfunction "GND_43") (pintype "power_in"))
      (node (ref "U2") (pin "5") (pinfunction "GND_5") (pintype "passive"))
      (node (ref "U2") (pin "7") (pinfunction "EP_7") (pintype "passive"))
      (node (ref "U3") (pin "2") (pinfunction "GND_2") (pintype "passive"))
      (node (ref "X1") (pin "2") (pinfunction "GND_2") (pintype "power_in"))
      (node (ref "X1") (pin "4") (pinfunction "GND_4") (pintype "power_in"))
    )
    (net (code "46") (name "Net-(LED1-C)") (class "Default")
      (node (ref "LED1") (pin "2") (pinfunction "C_2") (pintype "passive"))
      (node (ref "R5") (pin "2") (pinfunction "2_2") (pintype "passive"))
    )
    (net (code "47") (name "Net-(LED2-C)") (class "Default")
      (node (ref "LED2") (pin "2") (pinfunction "C_2") (pintype "passive"))
      (node (ref "R6") (pin "2") (pinfunction "2_2") (pintype "passive"))
    )
    (net (code "48") (name "Net-(LED3-K)") (class "Default")
      (node (ref "LED3") (pin "2") (pinfunction "K_2") (pintype "passive"))
      (node (ref "R11") (pin "2") (pinfunction "2_2") (pintype "passive"))
    )
    (net (code "49") (name "Net-(LED4-K)") (class "Default")
      (node (ref "LED4") (pin "2") (pinfunction "K_2") (pintype "passive"))
      (node (ref "R12") (pin "2") (pinfunction "2_2") (pintype "passive"))
    )
    (net (code "50") (name "Net-(U1-PB0_(SS{slash}PCINT0))") (class "Default")
      (node (ref "R6") (pin "1") (pinfunction "1_1") (pintype "passive"))
      (node (ref "U1") (pin "8") (pinfunction "PB0_(SS/PCINT0)_8") (pintype "bidirectional"))
    )
    (net (code "51") (name "Net-(U1-PD5_(XCK1{slash}~{CTS}))") (class "Default")
      (node (ref "R5") (pin "1") (pinfunction "1_1") (pintype "passive"))
      (node (ref "U1") (pin "22") (pinfunction "PD5_(XCK1/~{CTS})_22") (pintype "bidirectional"))
    )
    (net (code "52") (name "Net-(U2-ILIM)") (class "Default")
      (node (ref "R9") (pin "1") (pinfunction "1_1") (pintype "passive"))
      (node (ref "U2") (pin "2") (pinfunction "ILIM_2") (pintype "passive"))
    )
    (net (code "53") (name "Net-(U3-Y)") (class "Default")
      (node (ref "R12") (pin "1") (pinfunction "1_1") (pintype "passive"))
      (node (ref "U3") (pin "3") (pinfunction "Y_3") (pintype "passive"))
    )
    (net (code "54") (name "UGND") (class "Default")
      (node (ref "C10") (pin "2") (pinfunction "2_2") (pintype "passive"))
      (node (ref "NT2") (pin "2") (pintype "passive"))
      (node (ref "U1") (pin "5") (pinfunction "UGnd_5") (pintype "power_in"))
    )
    (net (code "55") (name "unconnected-(CN3-ID-Pad4)") (class "Default")
      (node (ref "CN3") (pin "4") (pinfunction "ID_4") (pintype "passive+no_connect"))
    )
    (net (code "56") (name "unconnected-(U1-PE2_(~{HWB})-Pad33)") (class "Default")
      (node (ref "U1") (pin "33") (pinfunction "PE2_(~{HWB})_33") (pintype "bidirectional+no_connect"))
    )
    (net (code "57") (name "unconnected-(U1-PF0_(ADC0)-Pad41)") (class "Default")
      (node (ref "U1") (pin "41") (pinfunction "PF0_(ADC0)_41") (pintype "bidirectional+no_connect"))
    )
    (net (code "58") (name "unconnected-(U1-PF1_(ADC1)-Pad40)") (class "Default")
      (node (ref "U1") (pin "40") (pinfunction "PF1_(ADC1)_40") (pintype "bidirectional+no_connect"))
    )
  )
)
